# 1wire.net
KiCad netlist of a schematic drawn in EAGLE
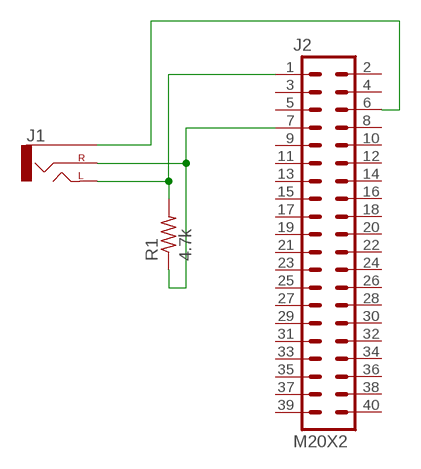
[diagram p0: schematic, sheet 1]

(export (version "E")
  (design (tool "Eeschema 10.0.6"))
  (components
    (comp (ref "J1")
      (value "AUDIO-JACKPTH")
      (footprint "eagle-import:AUDIO-JACK")
      (libsource (lib "eagle-import") (part "AUDIO-JACKPTH"))
    )
    (comp (ref "J2")
      (value "M20X2")
      (footprint "eagle-import:2X20")
      (libsource (lib "eagle-import") (part "M20X2"))
    )
    (comp (ref "R1")
      (value "4.7k")
      (footprint "eagle-import:R1206")
      (libsource (lib "eagle-import") (part "R-US_R1206"))
    )
  )
  (nets
    (net (code "1") (name "Net-(J1-LEFT)") (class "Default")
      (node (ref "J1") (pin "TIP") (pinfunction "LEFT_TIP") (pintype "bidirectional"))
      (node (ref "J2") (pin "1") (pinfunction "1_1") (pintype "passive"))
      (node (ref "R1") (pin "2") (pinfunction "2_2") (pintype "passive"))
    )
    (net (code "2") (name "Net-(J1-PadSLEEVE)") (class "Default")
      (node (ref "J1") (pin "SLEEVE") (pinfunction "SLEEVE_SLEEVE") (pintype "bidirectional"))
      (node (ref "J2") (pin "6") (pinfunction "6_6") (pintype "passive"))
    )
    (net (code "3") (name "Net-(J1-RIGHT)") (class "Default")
      (node (ref "J1") (pin "RING") (pinfunction "RIGHT_RING") (pintype "bidirectional"))
      (node (ref "J2") (pin "7") (pinfunction "7_7") (pintype "passive"))
      (node (ref "R1") (pin "1") (pinfunction "1_1") (pintype "passive"))
    )
    (net (code "4") (name "unconnected-(J2-Pad2)") (class "Default")
      (node (ref "J2") (pin "2") (pinfunction "2_2") (pintype "passive"))
    )
    (net (code "5") (name "unconnected-(J2-Pad3)") (class "Default")
      (node (ref "J2") (pin "3") (pinfunction "3_3") (pintype "passive"))
    )
    (net (code "6") (name "unconnected-(J2-Pad4)") (class "Default")
      (node (ref "J2") (pin "4") (pinfunction "4_4") (pintype "passive"))
    )
    (net (code "7") (name "unconnected-(J2-Pad5)") (class "Default")
      (node (ref "J2") (pin "5") (pinfunction "5_5") (pintype "passive"))
    )
    (net (code "8") (name "unconnected-(J2-Pad8)") (class "Default")
      (node (ref "J2") (pin "8") (pinfunction "8_8") (pintype "passive"))
    )
    (net (code "9") (name "unconnected-(J2-Pad9)") (class "Default")
      (node (ref "J2") (pin "9") (pinfunction "9_9") (pintype "passive"))
    )
    (net (code "10") (name "unconnected-(J2-Pad10)") (class "Default")
      (node (ref "J2") (pin "10") (pinfunction "10_10") (pintype "passive"))
    )
    (net (code "11") (name "unconnected-(J2-Pad11)") (class "Default")
      (node (ref "J2") (pin "11") (pinfunction "11_11") (pintype "passive"))
    )
    (net (code "12") (name "unconnected-(J2-Pad12)") (class "Default")
      (node (ref "J2") (pin "12") (pinfunction "12_12") (pintype "passive"))
    )
    (net (code "13") (name "unconnected-(J2-Pad13)") (class "Default")
      (node (ref "J2") (pin "13") (pinfunction "13_13") (pintype "passive"))
    )
    (net (code "14") (name "unconnected-(J2-Pad14)") (class "Default")
      (node (ref "J2") (pin "14") (pinfunction "14_14") (pintype "passive"))
    )
    (net (code "15") (name "unconnected-(J2-Pad15)") (class "Default")
      (node (ref "J2") (pin "15") (pinfunction "15_15") (pintype "passive"))
    )
    (net (code "16") (name "unconnected-(J2-Pad16)") (class "Default")
      (node (ref "J2") (pin "16") (pinfunction "16_16") (pintype "passive"))
    )
    (net (code "17") (name "unconnected-(J2-Pad17)") (class "Default")
      (node (ref "J2") (pin "17") (pinfunction "17_17") (pintype "passive"))
    )
    (net (code "18") (name "unconnected-(J2-Pad18)") (class "Default")
      (node (ref "J2") (pin "18") (pinfunction "18_18") (pintype "passive"))
    )
    (net (code "19") (name "unconnected-(J2-Pad19)") (class "Default")
      (node (ref "J2") (pin "19") (pinfunction "19_19") (pintype "passive"))
    )
    (net (code "20") (name "unconnected-(J2-Pad20)") (class "Default")
      (node (ref "J2") (pin "20") (pinfunction "20_20") (pintype "passive"))
    )
    (net (code "21") (name "unconnected-(J2-Pad21)") (class "Default")
      (node (ref "J2") (pin "21") (pinfunction "21_21") (pintype "passive"))
    )
    (net (code "22") (name "unconnected-(J2-Pad22)") (class "Default")
      (node (ref "J2") (pin "22") (pinfunction "22_22") (pintype "passive"))
    )
    (net (code "23") (name "unconnected-(J2-Pad23)") (class "Default")
      (node (ref "J2") (pin "23") (pinfunction "23_23") (pintype "passive"))
    )
    (net (code "24") (name "unconnected-(J2-Pad24)") (class "Default")
      (node (ref "J2") (pin "24") (pinfunction "24_24") (pintype "passive"))
    )
    (net (code "25") (name "unconnected-(J2-Pad25)") (class "Default")
      (node (ref "J2") (pin "25") (pinfunction "25_25") (pintype "passive"))
    )
    (net (code "26") (name "unconnected-(J2-Pad26)") (class "Default")
      (node (ref "J2") (pin "26") (pinfunction "26_26") (pintype "passive"))
    )
    (net (code "27") (name "unconnected-(J2-Pad27)") (class "Default")
      (node (ref "J2") (pin "27") (pinfunction "27_27") (pintype "passive"))
    )
    (net (code "28") (name "unconnected-(J2-Pad28)") (class "Default")
      (node (ref "J2") (pin "28") (pinfunction "28_28") (pintype "passive"))
    )
    (net (code "29") (name "unconnected-(J2-Pad29)") (class "Default")
      (node (ref "J2") (pin "29") (pinfunction "29_29") (pintype "passive"))
    )
    (net (code "30") (name "unconnected-(J2-Pad30)") (class "Default")
      (node (ref "J2") (pin "30") (pinfunction "30_30") (pintype "passive"))
    )
    (net (code "31") (name "unconnected-(J2-Pad31)") (class "Default")
      (node (ref "J2") (pin "31") (pinfunction "31_31") (pintype "passive"))
    )
    (net (code "32") (name "unconnected-(J2-Pad32)") (class "Default")
      (node (ref "J2") (pin "32") (pinfunction "32_32") (pintype "passive"))
    )
    (net (code "33") (name "unconnected-(J2-Pad33)") (class "Default")
      (node (ref "J2") (pin "33") (pinfunction "33_33") (pintype "passive"))
    )
    (net (code "34") (name "unconnected-(J2-Pad34)") (class "Default")
      (node (ref "J2") (pin "34") (pinfunction "34_34") (pintype "passive"))
    )
    (net (code "35") (name "unconnected-(J2-Pad35)") (class "Default")
      (node (ref "J2") (pin "35") (pinfunction "35_35") (pintype "passive"))
    )
    (net (code "36") (name "unconnected-(J2-Pad36)") (class "Default")
      (node (ref "J2") (pin "36") (pinfunction "36_36") (pintype "passive"))
    )
    (net (code "37") (name "unconnected-(J2-Pad37)") (class "Default")
      (node (ref "J2") (pin "37") (pinfunction "37_37") (pintype "passive"))
    )
    (net (code "38") (name "unconnected-(J2-Pad38)") (class "Default")
      (node (ref "J2") (pin "38") (pinfunction "38_38") (pintype "passive"))
    )
    (net (code "39") (name "unconnected-(J2-Pad39)") (class "Default")
      (node (ref "J2") (pin "39") (pinfunction "39_39") (pintype "passive"))
    )
    (net (code "40") (name "unconnected-(J2-Pad40)") (class "Default")
      (node (ref "J2") (pin "40") (pinfunction "40_40") (pintype "passive"))
    )
  )
)
